# SCH_ECG-business-card_2025-07-31.net
KiCad netlist of a schematic drawn in EasyEDA
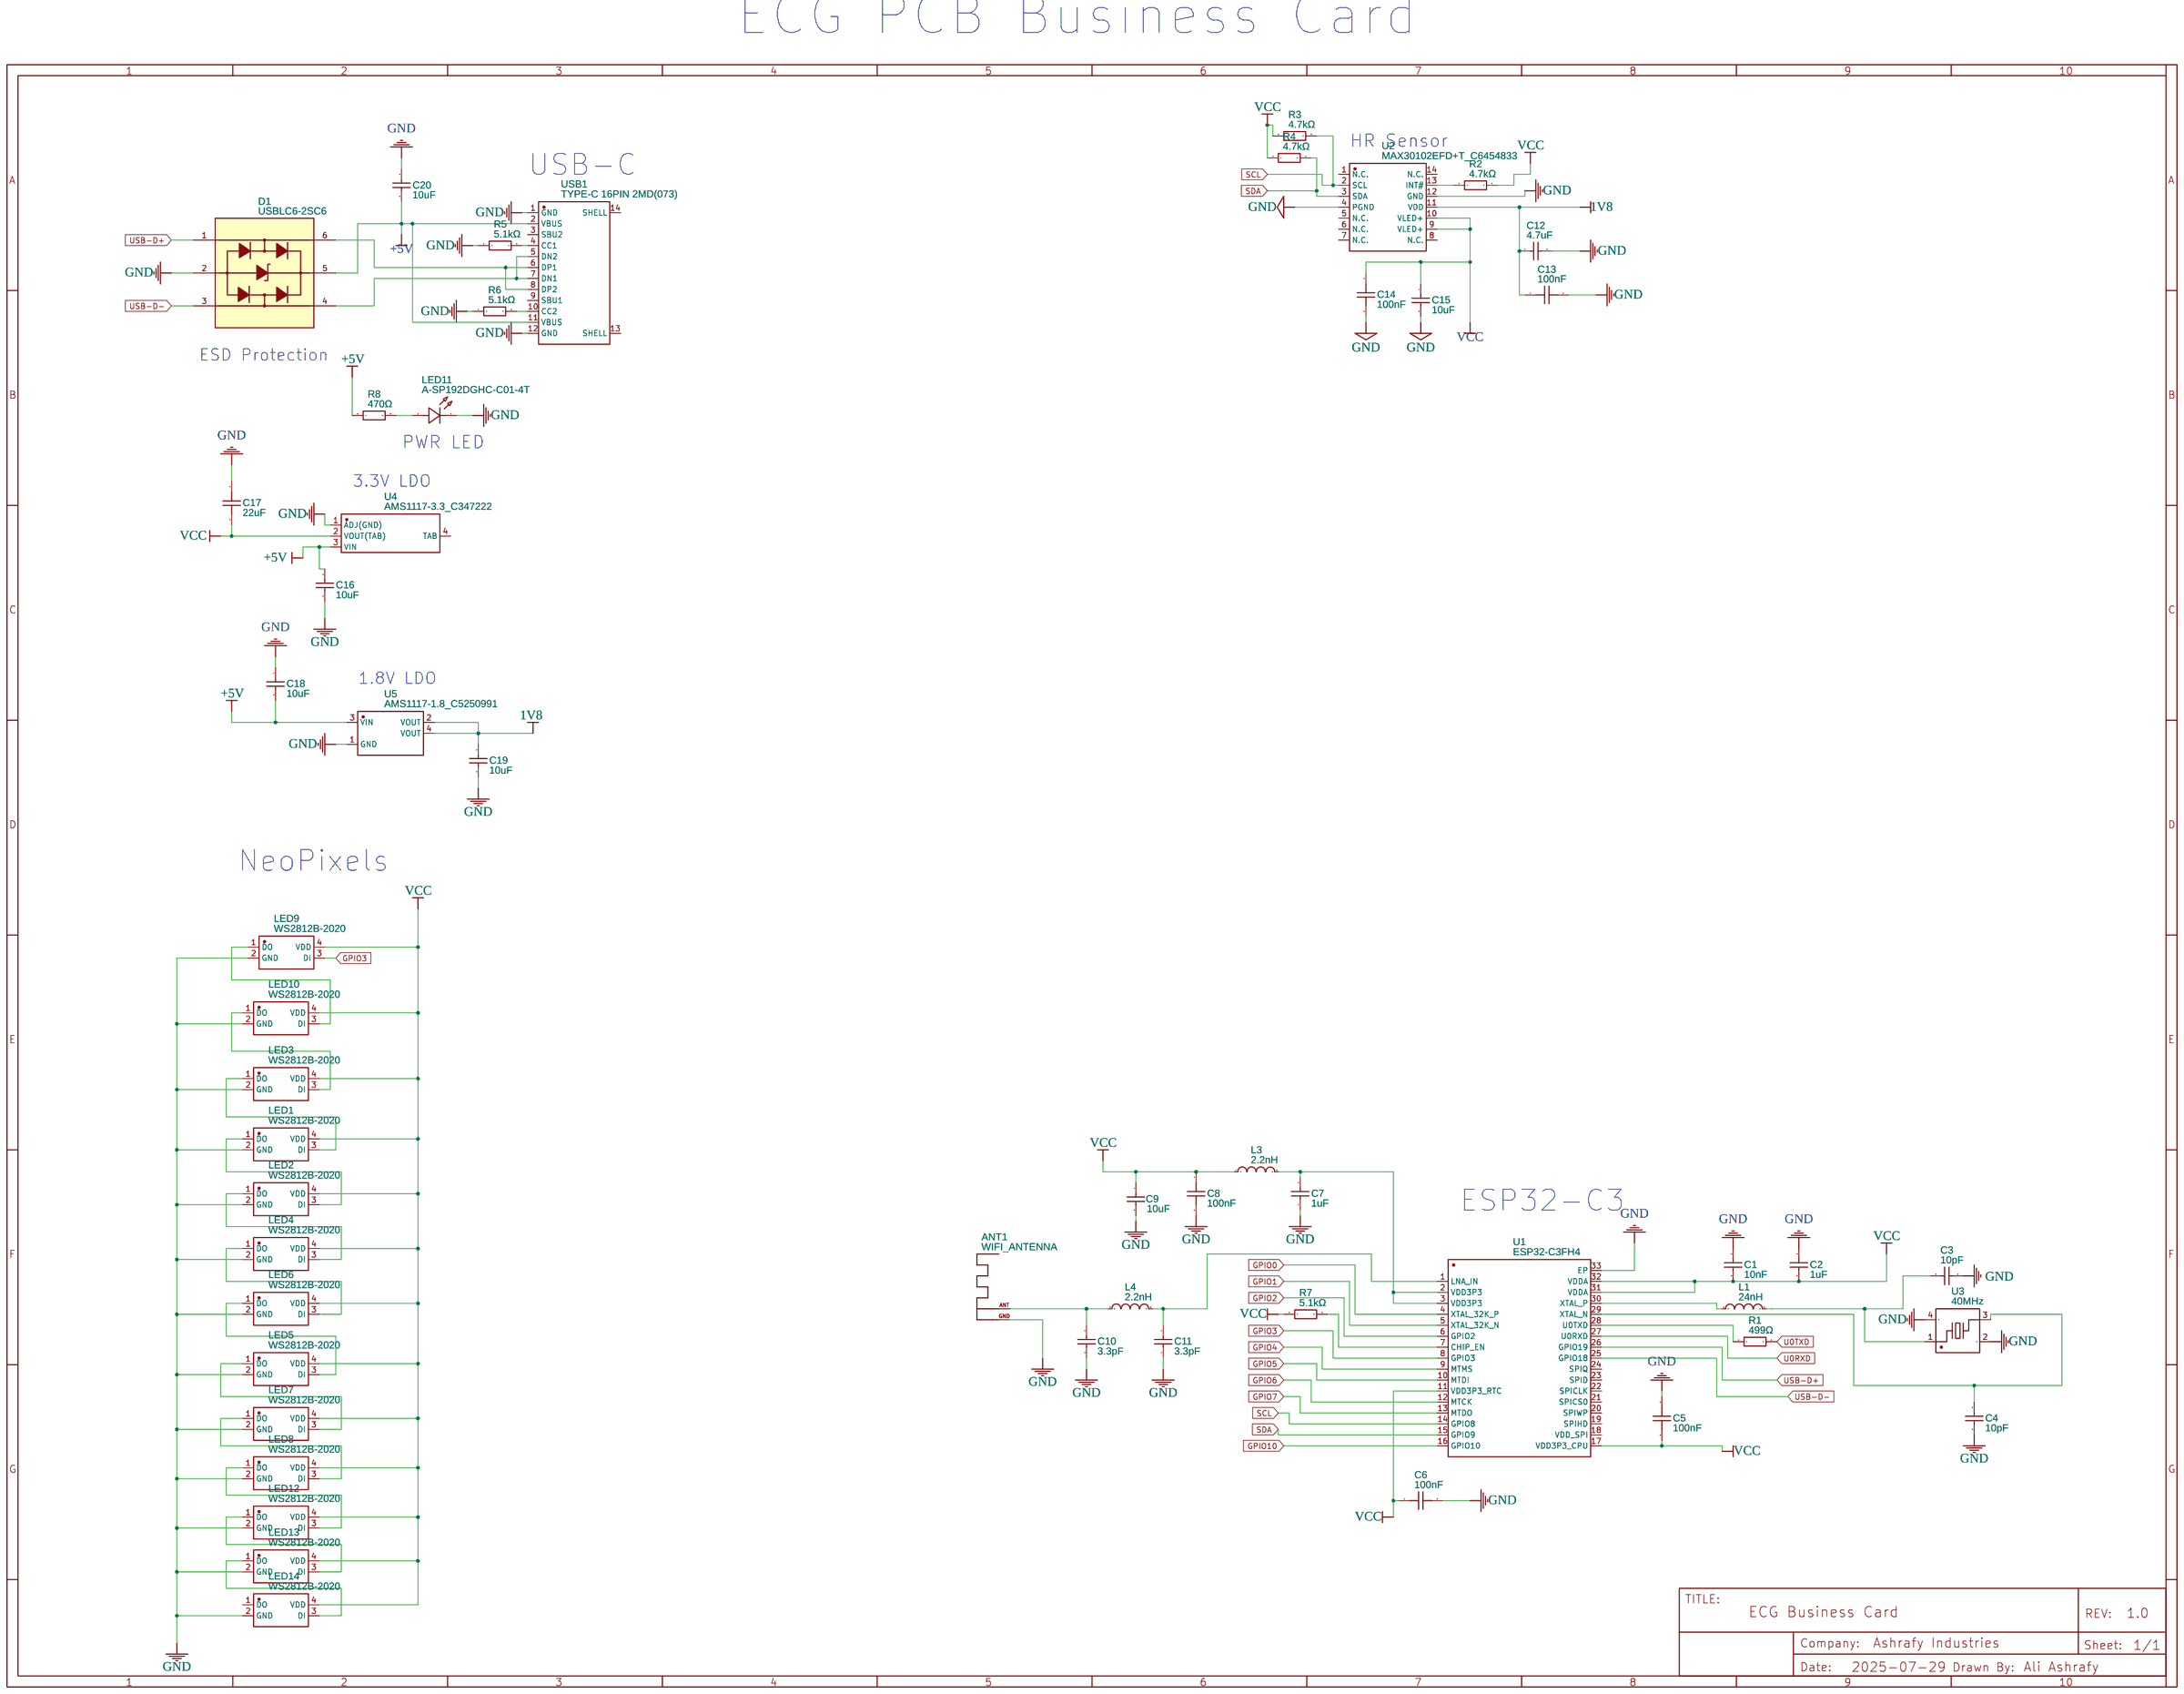
[diagram p0: schematic sheet]

(export (version "E")
  (design (tool "Eeschema 10.0.6"))
  (components
    (comp (ref "ANT1") (value "WIFI_ANTENNA") (libsource (lib "") (part "WIFI_ANTENNA")))
    (comp (ref "C1")
      (value "10nF")
      (fields
        (field (name "Manufacturer Part") "CC0603KRX7R9BB103")
        (field (name "Manufacturer") "YAGEO(国巨)")
      )
      (libsource (lib "") (part "CC0603KRX7R9BB103"))
    )
    (comp (ref "C2")
      (value "1uF")
      (fields
        (field (name "Manufacturer Part") "CL21B105KBFNNNE")
        (field (name "Manufacturer") "SAMSUNG(三星)")
      )
      (libsource (lib "") (part "CL21B105KBFNNNE"))
    )
    (comp (ref "C3")
      (value "10pF")
      (fields
        (field (name "Manufacturer Part") "GRM1555C1H100JA01D")
        (field (name "Manufacturer") "muRata(村田)")
      )
      (libsource (lib "") (part "GRM1555C1H100JA01D"))
    )
    (comp (ref "C4")
      (value "10pF")
      (fields
        (field (name "Manufacturer Part") "GRM1555C1H100JA01D")
        (field (name "Manufacturer") "muRata(村田)")
      )
      (libsource (lib "") (part "GRM1555C1H100JA01D_1"))
    )
    (comp (ref "C5")
      (value "100nF")
      (fields
        (field (name "Manufacturer Part") "CC0603KRX7R9BB104")
        (field (name "Manufacturer") "YAGEO(国巨)")
      )
      (libsource (lib "") (part "CC0603KRX7R9BB104"))
    )
    (comp (ref "C6")
      (value "100nF")
      (fields
        (field (name "Manufacturer Part") "CC0603KRX7R9BB104")
        (field (name "Manufacturer") "YAGEO(国巨)")
      )
      (libsource (lib "") (part "CC0603KRX7R9BB104_1"))
    )
    (comp (ref "C7")
      (value "1uF")
      (fields
        (field (name "Manufacturer Part") "CL21B105KBFNNNE")
        (field (name "Manufacturer") "SAMSUNG(三星)")
      )
      (libsource (lib "") (part "CL21B105KBFNNNE"))
    )
    (comp (ref "C8")
      (value "100nF")
      (fields
        (field (name "Manufacturer Part") "CC0603KRX7R9BB104")
        (field (name "Manufacturer") "YAGEO(国巨)")
      )
      (libsource (lib "") (part "CC0603KRX7R9BB104"))
    )
    (comp (ref "C9")
      (value "10uF")
      (fields
        (field (name "Manufacturer Part") "CL31A106KBHNNNE")
        (field (name "Manufacturer") "SAMSUNG(三星)")
      )
      (libsource (lib "") (part "CL31A106KBHNNNE"))
    )
    (comp (ref "C10")
      (value "3.3pF")
      (fields
        (field (name "Manufacturer Part") "GJM1555C1H3R3BB01D")
        (field (name "Manufacturer") "muRata(村田)")
      )
      (libsource (lib "") (part "GJM1555C1H3R3BB01D"))
    )
    (comp (ref "C11")
      (value "3.3pF")
      (fields
        (field (name "Manufacturer Part") "GJM1555C1H3R3BB01D")
        (field (name "Manufacturer") "muRata(村田)")
      )
      (libsource (lib "") (part "GJM1555C1H3R3BB01D"))
    )
    (comp (ref "C12")
      (value "4.7uF")
      (fields
        (field (name "Manufacturer Part") "CL10A475KP8NNNC")
        (field (name "Manufacturer") "SAMSUNG(三星)")
      )
      (libsource (lib "") (part "CL10A475KP8NNNC"))
    )
    (comp (ref "C13")
      (value "100nF")
      (fields
        (field (name "Manufacturer Part") "CC0603KRX7R9BB104")
        (field (name "Manufacturer") "YAGEO(国巨)")
      )
      (libsource (lib "") (part "CC0603KRX7R9BB104_1"))
    )
    (comp (ref "C14")
      (value "100nF")
      (fields
        (field (name "Manufacturer Part") "CC0603KRX7R9BB104")
        (field (name "Manufacturer") "YAGEO(国巨)")
      )
      (libsource (lib "") (part "CC0603KRX7R9BB104"))
    )
    (comp (ref "C15")
      (value "10uF")
      (fields
        (field (name "Manufacturer Part") "CL31A106KBHNNNE")
        (field (name "Manufacturer") "SAMSUNG(三星)")
      )
      (libsource (lib "") (part "CL31A106KBHNNNE"))
    )
    (comp (ref "C16")
      (value "10uF")
      (fields
        (field (name "Manufacturer Part") "CL31A106KBHNNNE")
        (field (name "Manufacturer") "SAMSUNG(三星)")
      )
      (libsource (lib "") (part "CL31A106KBHNNNE"))
    )
    (comp (ref "C17")
      (value "22uF")
      (fields
        (field (name "Manufacturer Part") "CL21A226MAYNNNE")
        (field (name "Manufacturer") "SAMSUNG(三星)")
      )
      (libsource (lib "") (part "CL21A226MAYNNNE"))
    )
    (comp (ref "C18")
      (value "10uF")
      (fields
        (field (name "Manufacturer Part") "CL31A106KBHNNNE")
        (field (name "Manufacturer") "SAMSUNG(三星)")
      )
      (libsource (lib "") (part "CL31A106KBHNNNE"))
    )
    (comp (ref "C19")
      (value "10uF")
      (fields
        (field (name "Manufacturer Part") "CL31A106KBHNNNE")
        (field (name "Manufacturer") "SAMSUNG(三星)")
      )
      (libsource (lib "") (part "CL31A106KBHNNNE"))
    )
    (comp (ref "C20")
      (value "10uF")
      (fields
        (field (name "Manufacturer Part") "CL31A106KBHNNNE")
        (field (name "Manufacturer") "SAMSUNG(三星)")
      )
      (libsource (lib "") (part "CL31A106KBHNNNE"))
    )
    (comp (ref "D1")
      (value "USBLC6-2SC6")
      (fields (field (name "Manufacturer") "ST(意法半导体)"))
      (libsource (lib "") (part "USBLC6-2SC6"))
    )
    (comp (ref "L1")
      (value "24nH")
      (fields (field (name "Manufacturer Part") "LQP03TN24NH02D") (field (name "Manufacturer") "muRata(村田)"))
      (libsource (lib "") (part "LQP03TN24NH02D"))
    )
    (comp (ref "L3")
      (value "2.2nH")
      (fields (field (name "Manufacturer Part") "LQG15HS2N2S02D") (field (name "Manufacturer") "muRata(村田)"))
      (libsource (lib "") (part "LQG15HS2N2S02D"))
    )
    (comp (ref "L4")
      (value "2.2nH")
      (fields (field (name "Manufacturer Part") "LQG15HS2N2S02D") (field (name "Manufacturer") "muRata(村田)"))
      (libsource (lib "") (part "LQG15HS2N2S02D_1"))
    )
    (comp (ref "LED1")
      (value "WS2812B-2020")
      (fields (field (name "Manufacturer") "worldsemi"))
      (libsource (lib "") (part "WS2812B-2020"))
    )
    (comp (ref "LED2")
      (value "WS2812B-2020")
      (fields (field (name "Manufacturer") "worldsemi"))
      (libsource (lib "") (part "WS2812B-2020"))
    )
    (comp (ref "LED3")
      (value "WS2812B-2020")
      (fields (field (name "Manufacturer") "worldsemi"))
      (libsource (lib "") (part "WS2812B-2020"))
    )
    (comp (ref "LED4")
      (value "WS2812B-2020")
      (fields (field (name "Manufacturer") "worldsemi"))
      (libsource (lib "") (part "WS2812B-2020"))
    )
    (comp (ref "LED5")
      (value "WS2812B-2020")
      (fields (field (name "Manufacturer") "worldsemi"))
      (libsource (lib "") (part "WS2812B-2020"))
    )
    (comp (ref "LED6")
      (value "WS2812B-2020")
      (fields (field (name "Manufacturer") "worldsemi"))
      (libsource (lib "") (part "WS2812B-2020"))
    )
    (comp (ref "LED7")
      (value "WS2812B-2020")
      (fields (field (name "Manufacturer") "worldsemi"))
      (libsource (lib "") (part "WS2812B-2020"))
    )
    (comp (ref "LED8")
      (value "WS2812B-2020")
      (fields (field (name "Manufacturer") "worldsemi"))
      (libsource (lib "") (part "WS2812B-2020"))
    )
    (comp (ref "LED9")
      (value "WS2812B-2020")
      (fields (field (name "Manufacturer") "worldsemi"))
      (libsource (lib "") (part "WS2812B-2020"))
    )
    (comp (ref "LED10")
      (value "WS2812B-2020")
      (fields (field (name "Manufacturer") "worldsemi"))
      (libsource (lib "") (part "WS2812B-2020"))
    )
    (comp (ref "LED11")
      (value "A-SP192DGHC-C01-4T")
      (fields (field (name "Manufacturer") "Amicc(欧密格光电)"))
      (libsource (lib "") (part "A-SP192DGHC-C01-4T"))
    )
    (comp (ref "LED12")
      (value "WS2812B-2020")
      (fields (field (name "Manufacturer") "worldsemi"))
      (libsource (lib "") (part "WS2812B-2020"))
    )
    (comp (ref "LED13")
      (value "WS2812B-2020")
      (fields (field (name "Manufacturer") "worldsemi"))
      (libsource (lib "") (part "WS2812B-2020"))
    )
    (comp (ref "LED14")
      (value "WS2812B-2020")
      (fields (field (name "Manufacturer") "worldsemi"))
      (libsource (lib "") (part "WS2812B-2020"))
    )
    (comp (ref "R1")
      (value "499Ω")
      (fields (field (name "Manufacturer Part") "RC0402FR-07499RL") (field (name "Manufacturer") "YAGEO(国巨)"))
      (libsource (lib "") (part "RC0402FR-07499RL"))
    )
    (comp (ref "R2")
      (value "4.7kΩ")
      (fields (field (name "Manufacturer Part") "RC0603FR-074K7L") (field (name "Manufacturer") "YAGEO(国巨)"))
      (libsource (lib "") (part "RC0603FR-074K7L"))
    )
    (comp (ref "R3")
      (value "4.7kΩ")
      (fields (field (name "Manufacturer Part") "RC0603FR-074K7L") (field (name "Manufacturer") "YAGEO(国巨)"))
      (libsource (lib "") (part "RC0603FR-074K7L"))
    )
    (comp (ref "R4")
      (value "4.7kΩ")
      (fields (field (name "Manufacturer Part") "RC0603FR-074K7L") (field (name "Manufacturer") "YAGEO(国巨)"))
      (libsource (lib "") (part "RC0603FR-074K7L"))
    )
    (comp (ref "R5")
      (value "5.1kΩ")
      (fields (field (name "Manufacturer Part") "RC0603FR-075K1L") (field (name "Manufacturer") "YAGEO(国巨)"))
      (libsource (lib "") (part "RC0603FR-075K1L"))
    )
    (comp (ref "R6")
      (value "5.1kΩ")
      (fields (field (name "Manufacturer Part") "RC0603FR-075K1L") (field (name "Manufacturer") "YAGEO(国巨)"))
      (libsource (lib "") (part "RC0603FR-075K1L"))
    )
    (comp (ref "R7")
      (value "5.1kΩ")
      (fields (field (name "Manufacturer Part") "RC0603FR-075K1L") (field (name "Manufacturer") "YAGEO(国巨)"))
      (libsource (lib "") (part "RC0603FR-075K1L"))
    )
    (comp (ref "R8")
      (value "470Ω")
      (fields (field (name "Manufacturer Part") "RC0603FR-07470RL") (field (name "Manufacturer") "YAGEO(国巨)"))
      (libsource (lib "") (part "RC0603FR-07470RL"))
    )
    (comp (ref "U1")
      (value "ESP32-C3FH4")
      (fields (field (name "Manufacturer") "ESPRESSIF(乐鑫)"))
      (libsource (lib "") (part "ESP32-C3FH4"))
    )
    (comp (ref "U2")
      (value "MAX30102EFD+T_C6454833")
      (fields
        (field (name "Manufacturer Part") "MAX30102EFD+T")
        (field (name "Manufacturer") "ADI(亚德诺)/MAXIM(美信)")
      )
      (libsource (lib "") (part "MAX30102EFD+T_C6454833"))
    )
    (comp (ref "U3")
      (value "40MHz")
      (fields (field (name "Manufacturer Part") "L327S400H11L") (field (name "Manufacturer") "Lucki(蓝晶)"))
      (libsource (lib "") (part "L327S400H11L"))
    )
    (comp (ref "U4")
      (value "AMS1117-3.3_C347222")
      (fields (field (name "Manufacturer Part") "AMS1117-3.3") (field (name "Manufacturer") "UMW(友台半导体)"))
      (libsource (lib "") (part "AMS1117-3.3_C347222"))
    )
    (comp (ref "U5")
      (value "AMS1117-1.8_C5250991")
      (fields (field (name "Manufacturer Part") "AMS1117-1.8") (field (name "Manufacturer") "TWGMC(台湾迪嘉)"))
      (libsource (lib "") (part "AMS1117-1.8_C5250991"))
    )
    (comp (ref "USB1")
      (value "TYPE-C 16PIN 2MD(073)")
      (fields (field (name "Manufacturer") "SHOU HAN(首韩)"))
      (libsource (lib "") (part "TYPE-C 16PIN 2MD(073)"))
    )
  )
  (nets
    (net (code "1") (name "+5V") (class "Default")
      (node (ref "C16") (pin "1") (pinfunction "1_1") (pintype "input"))
      (node (ref "C18") (pin "2") (pinfunction "2_2") (pintype "input"))
      (node (ref "C20") (pin "2") (pinfunction "2_2") (pintype "input"))
      (node (ref "D1") (pin "5") (pinfunction "5_5") (pintype "input"))
      (node (ref "R8") (pin "1") (pinfunction "1_1") (pintype "input"))
      (node (ref "U4") (pin "3") (pinfunction "VIN_3") (pintype "unspecified"))
      (node (ref "U5") (pin "3") (pinfunction "VIN_3") (pintype "unspecified"))
      (node (ref "USB1") (pin "11") (pinfunction "VBUS_11") (pintype "unspecified"))
      (node (ref "USB1") (pin "2") (pinfunction "VBUS_2") (pintype "unspecified"))
    )
    (net (code "2") (name "1V8") (class "Default")
      (node (ref "C12") (pin "1") (pinfunction "1_1") (pintype "input"))
      (node (ref "C13") (pin "1") (pinfunction "1_1") (pintype "unspecified"))
      (node (ref "C19") (pin "1") (pinfunction "1_1") (pintype "input"))
      (node (ref "U2") (pin "11") (pinfunction "VDD_11") (pintype "unspecified"))
      (node (ref "U5") (pin "2") (pinfunction "VOUT_2") (pintype "unspecified"))
      (node (ref "U5") (pin "4") (pinfunction "VOUT_4") (pintype "unspecified"))
    )
    (net (code "3") (name "GND") (class "Default")
      (node (ref "ANT1") (pin "GND") (pinfunction "GND_GND") (pintype "unspecified"))
      (node (ref "C1") (pin "2") (pinfunction "2_2") (pintype "input"))
      (node (ref "C10") (pin "1") (pinfunction "1_1") (pintype "input"))
      (node (ref "C11") (pin "1") (pinfunction "1_1") (pintype "input"))
      (node (ref "C12") (pin "2") (pinfunction "2_2") (pintype "input"))
      (node (ref "C13") (pin "2") (pinfunction "2_2") (pintype "unspecified"))
      (node (ref "C14") (pin "2") (pinfunction "2_2") (pintype "unspecified"))
      (node (ref "C15") (pin "2") (pinfunction "2_2") (pintype "input"))
      (node (ref "C16") (pin "2") (pinfunction "2_2") (pintype "input"))
      (node (ref "C17") (pin "1") (pinfunction "1_1") (pintype "unspecified"))
      (node (ref "C18") (pin "1") (pinfunction "1_1") (pintype "input"))
      (node (ref "C19") (pin "2") (pinfunction "2_2") (pintype "input"))
      (node (ref "C2") (pin "2") (pinfunction "2_2") (pintype "input"))
      (node (ref "C20") (pin "1") (pinfunction "1_1") (pintype "input"))
      (node (ref "C3") (pin "2") (pinfunction "2_2") (pintype "input"))
      (node (ref "C4") (pin "2") (pinfunction "2_2") (pintype "input"))
      (node (ref "C5") (pin "1") (pinfunction "1_1") (pintype "unspecified"))
      (node (ref "C6") (pin "2") (pinfunction "2_2") (pintype "unspecified"))
      (node (ref "C7") (pin "1") (pinfunction "1_1") (pintype "input"))
      (node (ref "C8") (pin "2") (pinfunction "2_2") (pintype "unspecified"))
      (node (ref "C9") (pin "2") (pinfunction "2_2") (pintype "input"))
      (node (ref "D1") (pin "2") (pinfunction "2_2") (pintype "input"))
      (node (ref "LED1") (pin "2") (pinfunction "GND_2") (pintype "unspecified"))
      (node (ref "LED10") (pin "2") (pinfunction "GND_2") (pintype "unspecified"))
      (node (ref "LED11") (pin "2") (pinfunction "K_2") (pintype "unspecified"))
      (node (ref "LED12") (pin "2") (pinfunction "GND_2") (pintype "unspecified"))
      (node (ref "LED13") (pin "2") (pinfunction "GND_2") (pintype "unspecified"))
      (node (ref "LED14") (pin "2") (pinfunction "GND_2") (pintype "unspecified"))
      (node (ref "LED2") (pin "2") (pinfunction "GND_2") (pintype "unspecified"))
      (node (ref "LED3") (pin "2") (pinfunction "GND_2") (pintype "unspecified"))
      (node (ref "LED4") (pin "2") (pinfunction "GND_2") (pintype "unspecified"))
      (node (ref "LED5") (pin "2") (pinfunction "GND_2") (pintype "unspecified"))
      (node (ref "LED6") (pin "2") (pinfunction "GND_2") (pintype "unspecified"))
      (node (ref "LED7") (pin "2") (pinfunction "GND_2") (pintype "unspecified"))
      (node (ref "LED8") (pin "2") (pinfunction "GND_2") (pintype "unspecified"))
      (node (ref "LED9") (pin "2") (pinfunction "GND_2") (pintype "unspecified"))
      (node (ref "R5") (pin "1") (pinfunction "1_1") (pintype "input"))
      (node (ref "R6") (pin "1") (pinfunction "1_1") (pintype "input"))
      (node (ref "U1") (pin "33") (pinfunction "EP_33") (pintype "unspecified"))
      (node (ref "U2") (pin "12") (pinfunction "GND_12") (pintype "unspecified"))
      (node (ref "U2") (pin "4") (pinfunction "PGND_4") (pintype "unspecified"))
      (node (ref "U3") (pin "2") (pinfunction "GND_2") (pintype "input"))
      (node (ref "U3") (pin "4") (pinfunction "GND_4") (pintype "input"))
      (node (ref "U4") (pin "1") (pinfunction "ADJ(GND)_1") (pintype "unspecified"))
      (node (ref "U5") (pin "1") (pinfunction "GND_1") (pintype "unspecified"))
      (node (ref "USB1") (pin "1") (pinfunction "GND_1") (pintype "unspecified"))
      (node (ref "USB1") (pin "12") (pinfunction "GND_12") (pintype "unspecified"))
    )
    (net (code "4") (name "GPIO0") (class "Default")
      (node (ref "U1") (pin "4") (pinfunction "XTAL_32K_P_4") (pintype "unspecified"))
    )
    (net (code "5") (name "GPIO1") (class "Default")
      (node (ref "U1") (pin "5") (pinfunction "XTAL_32K_N_5") (pintype "unspecified"))
    )
    (net (code "6") (name "GPIO2") (class "Default")
      (node (ref "U1") (pin "6") (pinfunction "GPIO2_6") (pintype "unspecified"))
    )
    (net (code "7") (name "GPIO3") (class "Default")
      (node (ref "LED9") (pin "3") (pinfunction "DI_3") (pintype "unspecified"))
      (node (ref "U1") (pin "8") (pinfunction "GPIO3_8") (pintype "unspecified"))
    )
    (net (code "8") (name "GPIO4") (class "Default")
      (node (ref "U1") (pin "9") (pinfunction "MTMS_9") (pintype "unspecified"))
    )
    (net (code "9") (name "GPIO5") (class "Default")
      (node (ref "U1") (pin "10") (pinfunction "MTDI_10") (pintype "unspecified"))
    )
    (net (code "10") (name "GPIO6") (class "Default")
      (node (ref "U1") (pin "12") (pinfunction "MTCK_12") (pintype "unspecified"))
    )
    (net (code "11") (name "GPIO7") (class "Default")
      (node (ref "U1") (pin "13") (pinfunction "MTDO_13") (pintype "unspecified"))
    )
    (net (code "12") (name "GPIO10") (class "Default")
      (node (ref "U1") (pin "16") (pinfunction "GPIO10_16") (pintype "unspecified"))
    )
    (net (code "13") (name "Net-(ANT1-PadANT)") (class "Default")
      (node (ref "ANT1") (pin "ANT") (pinfunction "ANT_ANT") (pintype "unspecified"))
      (node (ref "C10") (pin "2") (pinfunction "2_2") (pintype "input"))
      (node (ref "L4") (pin "1") (pinfunction "1_1") (pintype "unspecified"))
    )
    (net (code "14") (name "Net-(C3-Pad1)") (class "Default")
      (node (ref "C3") (pin "1") (pinfunction "1_1") (pintype "input"))
      (node (ref "L1") (pin "2") (pinfunction "2_2") (pintype "unspecified"))
      (node (ref "U3") (pin "1") (pinfunction "1_1") (pintype "input"))
    )
    (net (code "15") (name "Net-(C7-Pad2)") (class "Default")
      (node (ref "C7") (pin "2") (pinfunction "2_2") (pintype "input"))
      (node (ref "L3") (pin "2") (pinfunction "2_2") (pintype "unspecified"))
      (node (ref "U1") (pin "2") (pinfunction "VDD3P3_2") (pintype "unspecified"))
      (node (ref "U1") (pin "3") (pinfunction "VDD3P3_3") (pintype "unspecified"))
    )
    (net (code "16") (name "Net-(LED1-DI)") (class "Default")
      (node (ref "LED1") (pin "3") (pinfunction "DI_3") (pintype "unspecified"))
      (node (ref "LED3") (pin "1") (pinfunction "DO_1") (pintype "unspecified"))
    )
    (net (code "17") (name "Net-(LED1-DO)") (class "Default")
      (node (ref "LED1") (pin "1") (pinfunction "DO_1") (pintype "unspecified"))
      (node (ref "LED2") (pin "3") (pinfunction "DI_3") (pintype "unspecified"))
    )
    (net (code "18") (name "Net-(LED2-DO)") (class "Default")
      (node (ref "LED2") (pin "1") (pinfunction "DO_1") (pintype "unspecified"))
      (node (ref "LED4") (pin "3") (pinfunction "DI_3") (pintype "unspecified"))
    )
    (net (code "19") (name "Net-(LED4-DO)") (class "Default")
      (node (ref "LED4") (pin "1") (pinfunction "DO_1") (pintype "unspecified"))
      (node (ref "LED6") (pin "3") (pinfunction "DI_3") (pintype "unspecified"))
    )
    (net (code "20") (name "Net-(LED5-DI)") (class "Default")
      (node (ref "LED5") (pin "3") (pinfunction "DI_3") (pintype "unspecified"))
      (node (ref "LED6") (pin "1") (pinfunction "DO_1") (pintype "unspecified"))
    )
    (net (code "21") (name "Net-(LED5-DO)") (class "Default")
      (node (ref "LED5") (pin "1") (pinfunction "DO_1") (pintype "unspecified"))
      (node (ref "LED7") (pin "3") (pinfunction "DI_3") (pintype "unspecified"))
    )
    (net (code "22") (name "Net-(LED7-DO)") (class "Default")
      (node (ref "LED7") (pin "1") (pinfunction "DO_1") (pintype "unspecified"))
      (node (ref "LED8") (pin "3") (pinfunction "DI_3") (pintype "unspecified"))
    )
    (net (code "23") (name "Net-(LED10-DI)") (class "Default")
      (node (ref "LED10") (pin "3") (pinfunction "DI_3") (pintype "unspecified"))
      (node (ref "LED9") (pin "1") (pinfunction "DO_1") (pintype "unspecified"))
    )
    (net (code "24") (name "Net-(LED10-DO)") (class "Default")
      (node (ref "LED10") (pin "1") (pinfunction "DO_1") (pintype "unspecified"))
      (node (ref "LED3") (pin "3") (pinfunction "DI_3") (pintype "unspecified"))
    )
    (net (code "25") (name "Net-(LED11-A)") (class "Default")
      (node (ref "LED11") (pin "1") (pinfunction "A_1") (pintype "unspecified"))
      (node (ref "R8") (pin "2") (pinfunction "2_2") (pintype "input"))
    )
    (net (code "26") (name "Net-(LED12-DI)") (class "Default")
      (node (ref "LED12") (pin "3") (pinfunction "DI_3") (pintype "unspecified"))
      (node (ref "LED8") (pin "1") (pinfunction "DO_1") (pintype "unspecified"))
    )
    (net (code "27") (name "Net-(LED12-DO)") (class "Default")
      (node (ref "LED12") (pin "1") (pinfunction "DO_1") (pintype "unspecified"))
      (node (ref "LED13") (pin "3") (pinfunction "DI_3") (pintype "unspecified"))
    )
    (net (code "28") (name "Net-(LED13-DO)") (class "Default")
      (node (ref "LED13") (pin "1") (pinfunction "DO_1") (pintype "unspecified"))
      (node (ref "LED14") (pin "3") (pinfunction "DI_3") (pintype "unspecified"))
    )
    (net (code "29") (name "Net-(U1-CHIP_EN)") (class "Default")
      (node (ref "R7") (pin "2") (pinfunction "2_2") (pintype "input"))
      (node (ref "U1") (pin "7") (pinfunction "CHIP_EN_7") (pintype "unspecified"))
    )
    (net (code "30") (name "Net-(U1-LNA_IN)") (class "Default")
      (node (ref "C11") (pin "2") (pinfunction "2_2") (pintype "input"))
      (node (ref "L4") (pin "2") (pinfunction "2_2") (pintype "unspecified"))
      (node (ref "U1") (pin "1") (pinfunction "LNA_IN_1") (pintype "unspecified"))
    )
    (net (code "31") (name "Net-(U1-U0TXD)") (class "Default")
      (node (ref "R1") (pin "1") (pinfunction "1_1") (pintype "input"))
      (node (ref "U1") (pin "28") (pinfunction "U0TXD_28") (pintype "unspecified"))
    )
    (net (code "32") (name "Net-(U1-XTAL_N)") (class "Default")
      (node (ref "C4") (pin "1") (pinfunction "1_1") (pintype "input"))
      (node (ref "U1") (pin "29") (pinfunction "XTAL_N_29") (pintype "unspecified"))
      (node (ref "U3") (pin "3") (pinfunction "3_3") (pintype "input"))
    )
    (net (code "33") (name "Net-(U1-XTAL_P)") (class "Default")
      (node (ref "L1") (pin "1") (pinfunction "1_1") (pintype "unspecified"))
      (node (ref "U1") (pin "30") (pinfunction "XTAL_P_30") (pintype "unspecified"))
    )
    (net (code "34") (name "Net-(U2-INT#)") (class "Default")
      (node (ref "R2") (pin "1") (pinfunction "1_1") (pintype "input"))
      (node (ref "U2") (pin "13") (pinfunction "INT#_13") (pintype "unspecified"))
    )
    (net (code "35") (name "Net-(USB1-CC1)") (class "Default")
      (node (ref "R5") (pin "2") (pinfunction "2_2") (pintype "input"))
      (node (ref "USB1") (pin "4") (pinfunction "CC1_4") (pintype "unspecified"))
    )
    (net (code "36") (name "Net-(USB1-CC2)") (class "Default")
      (node (ref "R6") (pin "2") (pinfunction "2_2") (pintype "input"))
      (node (ref "USB1") (pin "10") (pinfunction "CC2_10") (pintype "unspecified"))
    )
    (net (code "37") (name "Net-(USB1-DN1)") (class "Default")
      (node (ref "D1") (pin "4") (pinfunction "4_4") (pintype "input"))
      (node (ref "USB1") (pin "5") (pinfunction "DN2_5") (pintype "unspecified"))
      (node (ref "USB1") (pin "7") (pinfunction "DN1_7") (pintype "unspecified"))
    )
    (net (code "38") (name "Net-(USB1-DP1)") (class "Default")
      (node (ref "D1") (pin "6") (pinfunction "6_6") (pintype "input"))
      (node (ref "USB1") (pin "6") (pinfunction "DP1_6") (pintype "unspecified"))
      (node (ref "USB1") (pin "8") (pinfunction "DP2_8") (pintype "unspecified"))
    )
    (net (code "39") (name "SCL") (class "Default")
      (node (ref "R3") (pin "2") (pinfunction "2_2") (pintype "input"))
      (node (ref "U1") (pin "14") (pinfunction "GPIO8_14") (pintype "unspecified"))
      (node (ref "U2") (pin "2") (pinfunction "SCL_2") (pintype "unspecified"))
    )
    (net (code "40") (name "SDA") (class "Default")
      (node (ref "R4") (pin "2") (pinfunction "2_2") (pintype "input"))
      (node (ref "U1") (pin "15") (pinfunction "GPIO9_15") (pintype "unspecified"))
      (node (ref "U2") (pin "3") (pinfunction "SDA_3") (pintype "unspecified"))
    )
    (net (code "41") (name "U0RXD") (class "Default")
      (node (ref "U1") (pin "27") (pinfunction "U0RXD_27") (pintype "unspecified"))
    )
    (net (code "42") (name "U0TXD") (class "Default")
      (node (ref "R1") (pin "2") (pinfunction "2_2") (pintype "input"))
    )
    (net (code "43") (name "USB-D+") (class "Default")
      (node (ref "D1") (pin "1") (pinfunction "1_1") (pintype "input"))
      (node (ref "U1") (pin "26") (pinfunction "GPIO19_26") (pintype "unspecified"))
    )
    (net (code "44") (name "USB-D-") (class "Default")
      (node (ref "D1") (pin "3") (pinfunction "3_3") (pintype "input"))
      (node (ref "U1") (pin "25") (pinfunction "GPIO18_25") (pintype "unspecified"))
    )
    (net (code "45") (name "VCC") (class "Default")
      (node (ref "C1") (pin "1") (pinfunction "1_1") (pintype "input"))
      (node (ref "C14") (pin "1") (pinfunction "1_1") (pintype "unspecified"))
      (node (ref "C15") (pin "1") (pinfunction "1_1") (pintype "input"))
      (node (ref "C17") (pin "2") (pinfunction "2_2") (pintype "unspecified"))
      (node (ref "C2") (pin "1") (pinfunction "1_1") (pintype "input"))
      (node (ref "C5") (pin "2") (pinfunction "2_2") (pintype "unspecified"))
      (node (ref "C6") (pin "1") (pinfunction "1_1") (pintype "unspecified"))
      (node (ref "C8") (pin "1") (pinfunction "1_1") (pintype "unspecified"))
      (node (ref "C9") (pin "1") (pinfunction "1_1") (pintype "input"))
      (node (ref "L3") (pin "1") (pinfunction "1_1") (pintype "unspecified"))
      (node (ref "LED1") (pin "4") (pinfunction "VDD_4") (pintype "unspecified"))
      (node (ref "LED10") (pin "4") (pinfunction "VDD_4") (pintype "unspecified"))
      (node (ref "LED12") (pin "4") (pinfunction "VDD_4") (pintype "unspecified"))
      (node (ref "LED13") (pin "4") (pinfunction "VDD_4") (pintype "unspecified"))
      (node (ref "LED14") (pin "4") (pinfunction "VDD_4") (pintype "unspecified"))
      (node (ref "LED2") (pin "4") (pinfunction "VDD_4") (pintype "unspecified"))
      (node (ref "LED3") (pin "4") (pinfunction "VDD_4") (pintype "unspecified"))
      (node (ref "LED4") (pin "4") (pinfunction "VDD_4") (pintype "unspecified"))
      (node (ref "LED5") (pin "4") (pinfunction "VDD_4") (pintype "unspecified"))
      (node (ref "LED6") (pin "4") (pinfunction "VDD_4") (pintype "unspecified"))
      (node (ref "LED7") (pin "4") (pinfunction "VDD_4") (pintype "unspecified"))
      (node (ref "LED8") (pin "4") (pinfunction "VDD_4") (pintype "unspecified"))
      (node (ref "LED9") (pin "4") (pinfunction "VDD_4") (pintype "unspecified"))
      (node (ref "R2") (pin "2") (pinfunction "2_2") (pintype "input"))
      (node (ref "R3") (pin "1") (pinfunction "1_1") (pintype "input"))
      (node (ref "R4") (pin "1") (pinfunction "1_1") (pintype "input"))
      (node (ref "R7") (pin "1") (pinfunction "1_1") (pintype "input"))
      (node (ref "U1") (pin "11") (pinfunction "VDD3P3_RTC_11") (pintype "unspecified"))
      (node (ref "U1") (pin "17") (pinfunction "VDD3P3_CPU_17") (pintype "unspecified"))
      (node (ref "U1") (pin "31") (pinfunction "VDDA_31") (pintype "unspecified"))
      (node (ref "U1") (pin "32") (pinfunction "VDDA_32") (pintype "unspecified"))
      (node (ref "U2") (pin "10") (pinfunction "VLED+_10") (pintype "unspecified"))
      (node (ref "U2") (pin "9") (pinfunction "VLED+_9") (pintype "unspecified"))
      (node (ref "U4") (pin "2") (pinfunction "VOUT(TAB)_2") (pintype "unspecified"))
    )
    (net (code "46") (name "unconnected-(LED14-DO-Pad1)") (class "Default")
      (node (ref "LED14") (pin "1") (pinfunction "DO_1") (pintype "unspecified"))
    )
    (net (code "47") (name "unconnected-(U1-SPICLK-Pad22)") (class "Default")
      (node (ref "U1") (pin "22") (pinfunction "SPICLK_22") (pintype "unspecified"))
    )
    (net (code "48") (name "unconnected-(U1-SPICS0-Pad21)") (class "Default")
      (node (ref "U1") (pin "21") (pinfunction "SPICS0_21") (pintype "unspecified"))
    )
    (net (code "49") (name "unconnected-(U1-SPID-Pad23)") (class "Default")
      (node (ref "U1") (pin "23") (pinfunction "SPID_23") (pintype "unspecified"))
    )
    (net (code "50") (name "unconnected-(U1-SPIHD-Pad19)") (class "Default")
      (node (ref "U1") (pin "19") (pinfunction "SPIHD_19") (pintype "unspecified"))
    )
    (net (code "51") (name "unconnected-(U1-SPIQ-Pad24)") (class "Default")
      (node (ref "U1") (pin "24") (pinfunction "SPIQ_24") (pintype "unspecified"))
    )
    (net (code "52") (name "unconnected-(U1-SPIWP-Pad20)") (class "Default")
      (node (ref "U1") (pin "20") (pinfunction "SPIWP_20") (pintype "unspecified"))
    )
    (net (code "53") (name "unconnected-(U1-VDD_SPI-Pad18)") (class "Default")
      (node (ref "U1") (pin "18") (pinfunction "VDD_SPI_18") (pintype "unspecified"))
    )
    (net (code "54") (name "unconnected-(U2-N.C.-Pad1)") (class "Default")
      (node (ref "U2") (pin "1") (pinfunction "N.C._1") (pintype "unspecified"))
    )
    (net (code "55") (name "unconnected-(U2-N.C.-Pad5)") (class "Default")
      (node (ref "U2") (pin "5") (pinfunction "N.C._5") (pintype "unspecified"))
    )
    (net (code "56") (name "unconnected-(U2-N.C.-Pad6)") (class "Default")
      (node (ref "U2") (pin "6") (pinfunction "N.C._6") (pintype "unspecified"))
    )
    (net (code "57") (name "unconnected-(U2-N.C.-Pad7)") (class "Default")
      (node (ref "U2") (pin "7") (pinfunction "N.C._7") (pintype "unspecified"))
    )
    (net (code "58") (name "unconnected-(U2-N.C.-Pad8)") (class "Default")
      (node (ref "U2") (pin "8") (pinfunction "N.C._8") (pintype "unspecified"))
    )
    (net (code "59") (name "unconnected-(U2-N.C.-Pad14)") (class "Default")
      (node (ref "U2") (pin "14") (pinfunction "N.C._14") (pintype "unspecified"))
    )
    (net (code "60") (name "unconnected-(U4-TAB-Pad4)") (class "Default")
      (node (ref "U4") (pin "4") (pinfunction "TAB_4") (pintype "unspecified"))
    )
    (net (code "61") (name "unconnected-(USB1-SBU1-Pad9)") (class "Default")
      (node (ref "USB1") (pin "9") (pinfunction "SBU1_9") (pintype "unspecified"))
    )
    (net (code "62") (name "unconnected-(USB1-SBU2-Pad3)") (class "Default")
      (node (ref "USB1") (pin "3") (pinfunction "SBU2_3") (pintype "unspecified"))
    )
    (net (code "63") (name "unconnected-(USB1-SHELL-Pad13)") (class "Default")
      (node (ref "USB1") (pin "13") (pinfunction "SHELL_13") (pintype "unspecified"))
    )
    (net (code "64") (name "unconnected-(USB1-SHELL-Pad14)") (class "Default")
      (node (ref "USB1") (pin "14") (pinfunction "SHELL_14") (pintype "unspecified"))
    )
  )
)
